# STM32F7.net
KiCad netlist of a schematic drawn in Altium Designer
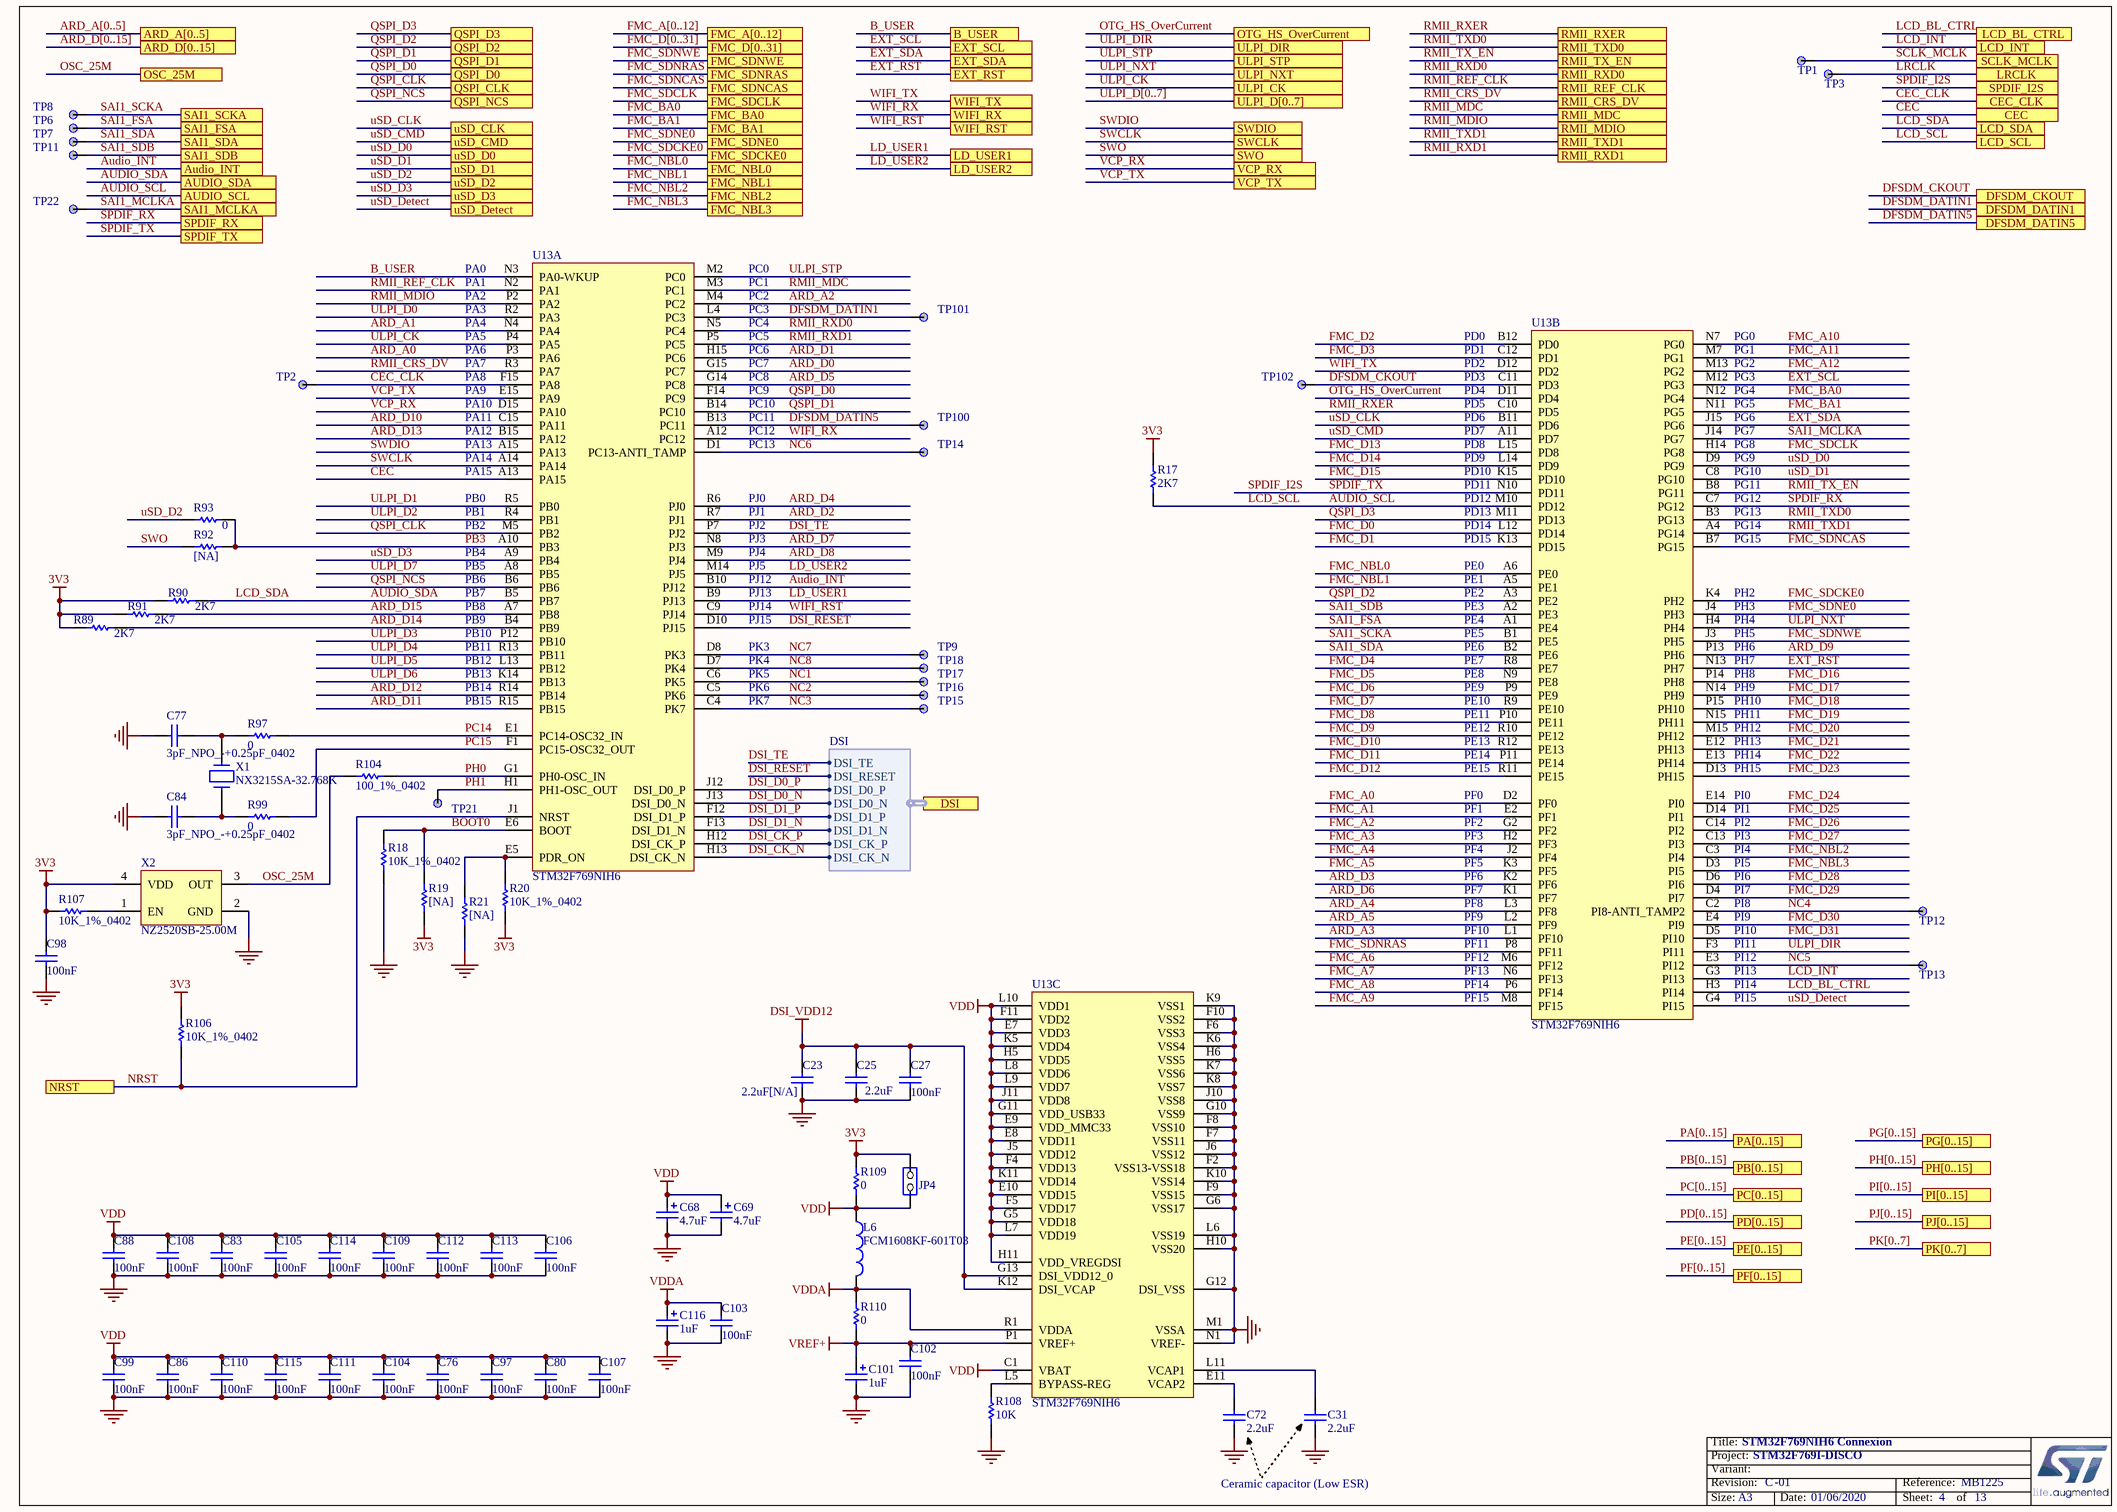
[diagram p0: STM32F7.SchDoc]

(export (version "E")
  (design (tool "Eeschema 10.0.6"))
  (components
    (comp (ref "C23")
      (value "2.2uF[N/A]")
      (footprint "1206C")
      (description "Capacitor,2.2uF,16V, X7R,10%,1206,YAGEO")
      (libsource (lib "MCD_TOOLS_CAPACITOR") (part "Cap_2.2uF_X7R_10%_1206"))
    )
    (comp (ref "C25")
      (value "2.2uF")
      (footprint "0603C")
      (description "Capacitor,2.2uF,10V, X5R,10%,0603,YAGEO")
      (libsource (lib "MCD_TOOLS_CAPACITOR") (part "Cap_2.2uF_X5R_10%_0603"))
    )
    (comp (ref "C27")
      (value "100nF")
      (footprint "0402C")
      (description "Capacitor,100nF,16V,X7R,10%,0402,YAGEO")
      (libsource (lib "MCD_TOOLS_CAPACITOR") (part "Cap_100nF_X7R_10%_0402"))
    )
    (comp (ref "C31")
      (value "2.2uF")
      (footprint "1206C")
      (description "Capacitor,2.2uF,16V, X7R,10%,1206,YAGEO")
      (libsource (lib "MCD_TOOLS") (part "Cap_2.2uF_X7R_10%_1206"))
    )
    (comp (ref "C68")
      (value "4.7uF")
      (footprint "TAN-A")
      (description "Polarized Capacitor,4.7uF,16V,10%,typeA,AVX")
      (libsource (lib "MCD_TOOLS") (part "Cap_4.7uF_POL_10%_TANA"))
    )
    (comp (ref "C69")
      (value "4.7uF")
      (footprint "TAN-A")
      (description "Polarized Capacitor,4.7uF,16V,10%,typeA,AVX")
      (libsource (lib "MCD_TOOLS") (part "Cap_4.7uF_POL_10%_TANA"))
    )
    (comp (ref "C72")
      (value "2.2uF")
      (footprint "1206C")
      (description "Capacitor,2.2uF,16V, X7R,10%,1206,YAGEO")
      (libsource (lib "MCD_TOOLS") (part "Cap_2.2uF_X7R_10%_1206"))
    )
    (comp (ref "C76")
      (value "100nF")
      (footprint "0402C")
      (description "Capacitor,100nF,16V,X7R,10%,0402,YAGEO")
      (libsource (lib "MCD_TOOLS") (part "Cap_100nF_X7R_10%_0402"))
    )
    (comp (ref "C77")
      (value "3pF_NPO_-+0.25pF_0402")
      (footprint "0402C")
      (description "Capacitor, 3pF, 16V, NPO, -+0.25pF, 0402, KEMET")
      (libsource (lib "MCD_TOOLS_CAPACITOR") (part "Cap_4.3pF_NPO_-+0.25pF_0402"))
    )
    (comp (ref "C80")
      (value "100nF")
      (footprint "0402C")
      (description "Capacitor,100nF,16V,X7R,10%,0402,YAGEO")
      (libsource (lib "MCD_TOOLS") (part "Cap_100nF_X7R_10%_0402"))
    )
    (comp (ref "C83")
      (value "100nF")
      (footprint "0402C")
      (description "Capacitor,100nF,16V,X7R,10%,0402,YAGEO")
      (libsource (lib "MCD_TOOLS") (part "Cap_100nF_X7R_10%_0402"))
    )
    (comp (ref "C84")
      (value "3pF_NPO_-+0.25pF_0402")
      (footprint "0402C")
      (description "Capacitor, 3pF, 16V, NPO, -+0.25pF, 0402, KEMET")
      (libsource (lib "MCD_TOOLS_CAPACITOR") (part "Cap_4.3pF_NPO_-+0.25pF_0402"))
    )
    (comp (ref "C86")
      (value "100nF")
      (footprint "0402C")
      (description "Capacitor,100nF,16V,X7R,10%,0402,YAGEO")
      (libsource (lib "MCD_TOOLS") (part "Cap_100nF_X7R_10%_0402"))
    )
    (comp (ref "C88")
      (value "100nF")
      (footprint "0402C")
      (description "Capacitor,100nF,16V,X7R,10%,0402,YAGEO")
      (libsource (lib "MCD_TOOLS") (part "Cap_100nF_X7R_10%_0402"))
    )
    (comp (ref "C97")
      (value "100nF")
      (footprint "0402C")
      (description "Capacitor,100nF,16V,X7R,10%,0402,YAGEO")
      (libsource (lib "MCD_TOOLS") (part "Cap_100nF_X7R_10%_0402"))
    )
    (comp (ref "C98")
      (value "100nF")
      (footprint "0402C")
      (description "Capacitor,100nF,16V,X7R,10%,0402,YAGEO")
      (libsource (lib "MCD_TOOLS") (part "Cap_100nF_X7R_10%_0402"))
    )
    (comp (ref "C99")
      (value "100nF")
      (footprint "0402C")
      (description "Capacitor,100nF,16V,X7R,10%,0402,YAGEO")
      (libsource (lib "MCD_TOOLS") (part "Cap_100nF_X7R_10%_0402"))
    )
    (comp (ref "C101")
      (value "1uF")
      (footprint "TAN-A")
      (description "Polarized Capacitor,1uF,16V,10%,typeA,AVX")
      (libsource (lib "MCD_TOOLS") (part "Cap_1uF_POL_10%_TANA"))
    )
    (comp (ref "C102")
      (value "100nF")
      (footprint "0402C")
      (description "Capacitor,100nF,16V,X7R,10%,0402,YAGEO")
      (libsource (lib "MCD_TOOLS") (part "Cap_100nF_X7R_10%_0402"))
    )
    (comp (ref "C103")
      (value "100nF")
      (footprint "0402C")
      (description "Capacitor,100nF,16V,X7R,10%,0402,YAGEO")
      (libsource (lib "MCD_TOOLS") (part "Cap_100nF_X7R_10%_0402"))
    )
    (comp (ref "C104")
      (value "100nF")
      (footprint "0402C")
      (description "Capacitor,100nF,16V,X7R,10%,0402,YAGEO")
      (libsource (lib "MCD_TOOLS") (part "Cap_100nF_X7R_10%_0402"))
    )
    (comp (ref "C105")
      (value "100nF")
      (footprint "0402C")
      (description "Capacitor,100nF,16V,X7R,10%,0402,YAGEO")
      (libsource (lib "MCD_TOOLS") (part "Cap_100nF_X7R_10%_0402"))
    )
    (comp (ref "C106")
      (value "100nF")
      (footprint "0402C")
      (description "Capacitor,100nF,16V,X7R,10%,0402,YAGEO")
      (libsource (lib "MCD_TOOLS") (part "Cap_100nF_X7R_10%_0402"))
    )
    (comp (ref "C107")
      (value "100nF")
      (footprint "0402C")
      (description "Capacitor,100nF,16V,X7R,10%,0402,YAGEO")
      (libsource (lib "MCD_TOOLS") (part "Cap_100nF_X7R_10%_0402"))
    )
    (comp (ref "C108")
      (value "100nF")
      (footprint "0402C")
      (description "Capacitor,100nF,16V,X7R,10%,0402,YAGEO")
      (libsource (lib "MCD_TOOLS") (part "Cap_100nF_X7R_10%_0402"))
    )
    (comp (ref "C109")
      (value "100nF")
      (footprint "0402C")
      (description "Capacitor,100nF,16V,X7R,10%,0402,YAGEO")
      (libsource (lib "MCD_TOOLS") (part "Cap_100nF_X7R_10%_0402"))
    )
    (comp (ref "C110")
      (value "100nF")
      (footprint "0402C")
      (description "Capacitor,100nF,16V,X7R,10%,0402,YAGEO")
      (libsource (lib "MCD_TOOLS") (part "Cap_100nF_X7R_10%_0402"))
    )
    (comp (ref "C111")
      (value "100nF")
      (footprint "0402C")
      (description "Capacitor,100nF,16V,X7R,10%,0402,YAGEO")
      (libsource (lib "MCD_TOOLS") (part "Cap_100nF_X7R_10%_0402"))
    )
    (comp (ref "C112")
      (value "100nF")
      (footprint "0402C")
      (description "Capacitor,100nF,16V,X7R,10%,0402,YAGEO")
      (libsource (lib "MCD_TOOLS") (part "Cap_100nF_X7R_10%_0402"))
    )
    (comp (ref "C113")
      (value "100nF")
      (footprint "0402C")
      (description "Capacitor,100nF,16V,X7R,10%,0402,YAGEO")
      (libsource (lib "MCD_TOOLS") (part "Cap_100nF_X7R_10%_0402"))
    )
    (comp (ref "C114")
      (value "100nF")
      (footprint "0402C")
      (description "Capacitor,100nF,16V,X7R,10%,0402,YAGEO")
      (libsource (lib "MCD_TOOLS") (part "Cap_100nF_X7R_10%_0402"))
    )
    (comp (ref "C115")
      (value "100nF")
      (footprint "0402C")
      (description "Capacitor,100nF,16V,X7R,10%,0402,YAGEO")
      (libsource (lib "MCD_TOOLS") (part "Cap_100nF_X7R_10%_0402"))
    )
    (comp (ref "C116")
      (value "1uF")
      (footprint "TAN-A")
      (description "Polarized Capacitor,1uF,16V,10%,typeA,AVX")
      (libsource (lib "MCD_TOOLS") (part "Cap_1uF_POL_10%_TANA"))
    )
    (comp (ref "JP4") (value "JP2") (footprint "SIP2") (libsource (lib "MCD_TOOLS_CONNECTOR") (part "JP2")))
    (comp (ref "L6")
      (value "FCM1608KF-601T03")
      (footprint "0603L")
      (description "Bead,600R,350mA,0603,FCM1608KF-601T03,Tai-tech")
      (libsource (lib "MCD_TOOLS") (part "BEAD_600R_350MA_0603"))
    )
    (comp (ref "R17")
      (value "2K7")
      (footprint "0402R")
      (description "Resistor,2K7,0402,1%,YAGEO")
      (libsource (lib "MCD_TOOLS") (part "Res_2K7_1%_0402"))
    )
    (comp (ref "R18")
      (value "10K_1%_0402")
      (footprint "0402R")
      (description "Resistor,10K,0402,1%,YAGEO")
      (libsource (lib "MCD_TOOLS") (part "Res_10K_1%_0402"))
    )
    (comp (ref "R19")
      (value "[NA]")
      (footprint "0402R")
      (description "Resistor,[NA],0402")
      (libsource (lib "MCD_TOOLS") (part "Res_NA_0402"))
    )
    (comp (ref "R20")
      (value "10K_1%_0402")
      (footprint "0402R")
      (description "Resistor,10K,0402,1%,YAGEO")
      (libsource (lib "MCD_TOOLS") (part "Res_10K_1%_0402"))
    )
    (comp (ref "R21")
      (value "[NA]")
      (footprint "0402R")
      (description "Resistor,[NA],0402")
      (libsource (lib "MCD_TOOLS") (part "Res_NA_0402"))
    )
    (comp (ref "R89")
      (value "2K7")
      (footprint "0402R")
      (description "Resistor,2K7,0402,1%,YAGEO")
      (libsource (lib "MCD_TOOLS") (part "Res_2K7_1%_0402"))
    )
    (comp (ref "R90")
      (value "2K7")
      (footprint "0402R")
      (description "Resistor,2K7,0402,1%,YAGEO")
      (libsource (lib "MCD_TOOLS") (part "Res_2K7_1%_0402"))
    )
    (comp (ref "R91")
      (value "2K7")
      (footprint "0402R")
      (description "Resistor,2K7,0402,1%,YAGEO")
      (libsource (lib "MCD_TOOLS") (part "Res_2K7_1%_0402"))
    )
    (comp (ref "R92")
      (value "[NA]")
      (footprint "0402R")
      (description "Resistor,[NA],0402")
      (libsource (lib "MCD_TOOLS_RESISTOR") (part "Res_NA_0402"))
    )
    (comp (ref "R93")
      (value "0")
      (footprint "0402R")
      (description "Resistor,0,0402,5%,YAGEO")
      (libsource (lib "MCD_TOOLS_RESISTOR") (part "Res_0_5%_0402"))
    )
    (comp (ref "R97")
      (value "0")
      (footprint "0402R")
      (description "Resistor,0,0402,5%,YAGEO")
      (libsource (lib "MCD_TOOLS") (part "Res_0_5%_0402"))
    )
    (comp (ref "R99")
      (value "0")
      (footprint "0402R")
      (description "Resistor,0,0402,5%,YAGEO")
      (libsource (lib "MCD_TOOLS") (part "Res_0_5%_0402"))
    )
    (comp (ref "R104")
      (value "100_1%_0402")
      (footprint "0402R")
      (description "Resistor,100,0402,1%,YAGEO")
      (libsource (lib "MCD_TOOLS") (part "Res_100_1%_0402"))
    )
    (comp (ref "R106")
      (value "10K_1%_0402")
      (footprint "0402R")
      (description "Resistor,10K,0402,1%,YAGEO")
      (libsource (lib "MCD_TOOLS") (part "Res_10K_1%_0402"))
    )
    (comp (ref "R107")
      (value "10K_1%_0402")
      (footprint "0402R")
      (description "Resistor,10K,0402,1%,YAGEO")
      (libsource (lib "MCD_TOOLS") (part "Res_10K_1%_0402"))
    )
    (comp (ref "R108")
      (value "10K")
      (footprint "0402R")
      (description "Resistor,10K,0402,1%,YAGEO")
      (libsource (lib "MCD_TOOLS") (part "Res_10K_1%_0402"))
    )
    (comp (ref "R109")
      (value "0")
      (footprint "0603R-GS")
      (description "Resistor,0,0603,5%,YAGEO")
      (libsource (lib "MCD_TOOLS") (part "Res_0_5%_0603"))
    )
    (comp (ref "R110")
      (value "0")
      (footprint "0603R-GS")
      (description "Resistor,0,0603,5%,YAGEO")
      (libsource (lib "MCD_TOOLS") (part "Res_0_5%_0603"))
    )
    (comp (ref "TP1")
      (value "TP")
      (footprint "TP_C40")
      (description "Test Point")
      (libsource (lib "MCD_TOOLS_CONNECTOR") (part "TP"))
    )
    (comp (ref "TP2")
      (value "TP")
      (footprint "TP_C40")
      (description "Test Point")
      (libsource (lib "MCD_TOOLS_CONNECTOR") (part "TP"))
    )
    (comp (ref "TP3")
      (value "TP")
      (footprint "TP_C40")
      (description "Test Point")
      (libsource (lib "MCD_TOOLS_CONNECTOR") (part "TP"))
    )
    (comp (ref "TP6")
      (value "TP")
      (footprint "TP_C40")
      (description "Test Point")
      (libsource (lib "MCD_TOOLS_CONNECTOR") (part "TP"))
    )
    (comp (ref "TP7")
      (value "TP")
      (footprint "TP_C40")
      (description "Test Point")
      (libsource (lib "MCD_TOOLS_CONNECTOR") (part "TP"))
    )
    (comp (ref "TP8")
      (value "TP")
      (footprint "TP_C40")
      (description "Test Point")
      (libsource (lib "MCD_TOOLS_CONNECTOR") (part "TP"))
    )
    (comp (ref "TP9")
      (value "TP")
      (footprint "TP_C40")
      (description "Test Point")
      (libsource (lib "MCD_TOOLS_CONNECTOR") (part "TP"))
    )
    (comp (ref "TP11")
      (value "TP")
      (footprint "TP_C40")
      (description "Test Point")
      (libsource (lib "MCD_TOOLS_CONNECTOR") (part "TP"))
    )
    (comp (ref "TP12")
      (value "TP")
      (footprint "TP_C40")
      (description "Test Point")
      (libsource (lib "MCD_TOOLS_CONNECTOR") (part "TP"))
    )
    (comp (ref "TP13")
      (value "TP")
      (footprint "TP_C40")
      (description "Test Point")
      (libsource (lib "MCD_TOOLS_CONNECTOR") (part "TP"))
    )
    (comp (ref "TP14")
      (value "TP")
      (footprint "TP_C40")
      (description "Test Point")
      (libsource (lib "MCD_TOOLS_CONNECTOR") (part "TP"))
    )
    (comp (ref "TP15")
      (value "TP")
      (footprint "TP_C40")
      (description "Test Point")
      (libsource (lib "MCD_TOOLS_CONNECTOR") (part "TP"))
    )
    (comp (ref "TP16")
      (value "TP")
      (footprint "TP_C40")
      (description "Test Point")
      (libsource (lib "MCD_TOOLS_CONNECTOR") (part "TP"))
    )
    (comp (ref "TP17")
      (value "TP")
      (footprint "TP_C40")
      (description "Test Point")
      (libsource (lib "MCD_TOOLS_CONNECTOR") (part "TP"))
    )
    (comp (ref "TP18")
      (value "TP")
      (footprint "TP_C40")
      (description "Test Point")
      (libsource (lib "MCD_TOOLS_CONNECTOR") (part "TP"))
    )
    (comp (ref "TP21")
      (value "TP")
      (footprint "TP_C40")
      (description "Test Point")
      (libsource (lib "MCD_TOOLS_CONNECTOR") (part "TP"))
    )
    (comp (ref "TP22")
      (value "TP")
      (footprint "TP_C40")
      (description "Test Point")
      (libsource (lib "MCD_TOOLS_CONNECTOR") (part "TP"))
    )
    (comp (ref "TP100")
      (value "TP")
      (footprint "TP_C40")
      (description "Test Point")
      (libsource (lib "MCD_TOOLS_CONNECTOR") (part "TP"))
    )
    (comp (ref "TP101")
      (value "TP")
      (footprint "TP_C40")
      (description "Test Point")
      (libsource (lib "MCD_TOOLS_CONNECTOR") (part "TP"))
    )
    (comp (ref "TP102")
      (value "TP")
      (footprint "TP_C40")
      (description "Test Point")
      (libsource (lib "MCD_TOOLS_CONNECTOR") (part "TP"))
    )
    (comp (ref "U13")
      (value "STM32F769NIH6")
      (footprint "BGA216_0R8_13X13")
      (description "STM32F769NIH6 (STM32F7 Big Birdie) TBGA216")
      (libsource (lib "MCD_TOOLS_MCU") (part "STM32F769NIH6U"))
    )
    (comp (ref "X1")
      (value "NX3215SA-32.768K")
      (footprint "XTAL_2SM_3R2X1R5")
      (description "Crystal 32.768kHz, 6pF, -+20PPM, R=50K, SMD")
      (libsource (lib "MCD_TOOLS") (part "XTAL_32K_NX3215SA"))
    )
    (comp (ref "X2")
      (value "NZ2520SB-25.00M")
      (footprint "OSC_4SM_2R5X2")
      (description "Oscillator 25.00Mhz, -+50PPM, 3.3V, Temp -55 to +125°C")
      (libsource (lib "MCD_TOOLS_MISCELLANEOUS") (part "OSC_25M_NZ2520SB"))
    )
  )
  (nets
    (net (code "165") (name "/ARD_A0") (class "Default")
      (node (ref "U13") (pin "P3") (pinfunction "PA6_P3") (pintype "passive"))
    )
    (net (code "166") (name "/ARD_A1") (class "Default")
      (node (ref "U13") (pin "N4") (pinfunction "PA4_N4") (pintype "passive"))
    )
    (net (code "167") (name "/ARD_A2") (class "Default")
      (node (ref "U13") (pin "M4") (pinfunction "PC2_M4") (pintype "passive"))
    )
    (net (code "168") (name "/ARD_A3") (class "Default")
      (node (ref "U13") (pin "L1") (pinfunction "PF10_L1") (pintype "passive"))
    )
    (net (code "169") (name "/ARD_A4") (class "Default")
      (node (ref "U13") (pin "L3") (pinfunction "PF8_L3") (pintype "passive"))
    )
    (net (code "170") (name "/ARD_A5") (class "Default")
      (node (ref "U13") (pin "L2") (pinfunction "PF9_L2") (pintype "passive"))
    )
    (net (code "172") (name "/ARD_D0") (class "Default")
      (node (ref "U13") (pin "G15") (pinfunction "PC7_G15") (pintype "passive"))
    )
    (net (code "173") (name "/ARD_D1") (class "Default")
      (node (ref "U13") (pin "H15") (pinfunction "PC6_H15") (pintype "passive"))
    )
    (net (code "174") (name "/ARD_D2") (class "Default")
      (node (ref "U13") (pin "R7") (pinfunction "PJ1_R7") (pintype "passive"))
    )
    (net (code "175") (name "/ARD_D3") (class "Default")
      (node (ref "U13") (pin "K2") (pinfunction "PF6_K2") (pintype "passive"))
    )
    (net (code "176") (name "/ARD_D4") (class "Default")
      (node (ref "U13") (pin "R6") (pinfunction "PJ0_R6") (pintype "passive"))
    )
    (net (code "177") (name "/ARD_D5") (class "Default")
      (node (ref "U13") (pin "G14") (pinfunction "PC8_G14") (pintype "passive"))
    )
    (net (code "178") (name "/ARD_D6") (class "Default")
      (node (ref "U13") (pin "K1") (pinfunction "PF7_K1") (pintype "passive"))
    )
    (net (code "179") (name "/ARD_D7") (class "Default")
      (node (ref "U13") (pin "N8") (pinfunction "PJ3_N8") (pintype "passive"))
    )
    (net (code "180") (name "/ARD_D8") (class "Default")
      (node (ref "U13") (pin "M9") (pinfunction "PJ4_M9") (pintype "passive"))
    )
    (net (code "181") (name "/ARD_D9") (class "Default")
      (node (ref "U13") (pin "P13") (pinfunction "PH6_P13") (pintype "passive"))
    )
    (net (code "182") (name "/ARD_D10") (class "Default")
      (node (ref "U13") (pin "C15") (pinfunction "PA11_C15") (pintype "passive"))
    )
    (net (code "183") (name "/ARD_D11") (class "Default")
      (node (ref "U13") (pin "R15") (pinfunction "PB15_R15") (pintype "passive"))
    )
    (net (code "184") (name "/ARD_D12") (class "Default")
      (node (ref "U13") (pin "R14") (pinfunction "PB14_R14") (pintype "passive"))
    )
    (net (code "185") (name "/ARD_D13") (class "Default")
      (node (ref "U13") (pin "B15") (pinfunction "PA12_B15") (pintype "passive"))
    )
    (net (code "186") (name "/ARD_D14") (class "Default")
      (node (ref "R89") (pin "2") (pinfunction "2_2") (pintype "passive"))
      (node (ref "U13") (pin "B4") (pinfunction "PB9_B4") (pintype "passive"))
    )
    (net (code "187") (name "/ARD_D15") (class "Default")
      (node (ref "R91") (pin "2") (pinfunction "2_2") (pintype "passive"))
      (node (ref "U13") (pin "A7") (pinfunction "PB8_A7") (pintype "passive"))
    )
    (net (code "189") (name "/AUDIO_SCL") (class "Default")
      (node (ref "R17") (pin "1") (pinfunction "1_1") (pintype "passive"))
      (node (ref "U13") (pin "M10") (pinfunction "PD12_M10") (pintype "passive"))
    )
    (net (code "190") (name "/AUDIO_SDA") (class "Default")
      (node (ref "R90") (pin "2") (pinfunction "2_2") (pintype "passive"))
      (node (ref "U13") (pin "B5") (pinfunction "PB7_B5") (pintype "passive"))
    )
    (net (code "191") (name "/Audio_INT") (class "Default")
      (node (ref "U13") (pin "B10") (pinfunction "PJ12_B10") (pintype "passive"))
    )
    (net (code "192") (name "/BOOT0") (class "Default")
      (node (ref "R18") (pin "2") (pinfunction "2_2") (pintype "passive"))
      (node (ref "R19") (pin "2") (pinfunction "2_2") (pintype "passive"))
      (node (ref "U13") (pin "E6") (pinfunction "BOOT_E6") (pintype "passive"))
    )
    (net (code "193") (name "/B_USER") (class "Default")
      (node (ref "U13") (pin "N3") (pinfunction "PA0-WKUP_N3") (pintype "passive"))
    )
    (net (code "194") (name "/CEC") (class "Default")
      (node (ref "U13") (pin "A13") (pinfunction "PA15_A13") (pintype "passive"))
    )
    (net (code "195") (name "/CEC_CLK") (class "Default")
      (node (ref "TP2") (pin "1") (pinfunction "1_1") (pintype "passive"))
      (node (ref "U13") (pin "F15") (pinfunction "PA8_F15") (pintype "passive"))
    )
    (net (code "196") (name "/DFSDM_CKOUT") (class "Default")
      (node (ref "TP102") (pin "1") (pinfunction "1_1") (pintype "passive"))
      (node (ref "U13") (pin "C11") (pinfunction "PD3_C11") (pintype "passive"))
    )
    (net (code "197") (name "/DFSDM_DATIN1") (class "Default")
      (node (ref "TP101") (pin "1") (pinfunction "1_1") (pintype "passive"))
      (node (ref "U13") (pin "L4") (pinfunction "PC3_L4") (pintype "passive"))
    )
    (net (code "198") (name "/DFSDM_DATIN5") (class "Default")
      (node (ref "TP100") (pin "1") (pinfunction "1_1") (pintype "passive"))
      (node (ref "U13") (pin "B13") (pinfunction "PC11_B13") (pintype "passive"))
    )
    (net (code "199") (name "/DSI_CK_N") (class "Default")
      (node (ref "U13") (pin "H13") (pinfunction "DSI_CK_N_H13") (pintype "passive"))
    )
    (net (code "200") (name "/DSI_CK_P") (class "Default")
      (node (ref "U13") (pin "H12") (pinfunction "DSI_CK_P_H12") (pintype "passive"))
    )
    (net (code "201") (name "/DSI_D0_N") (class "Default")
      (node (ref "U13") (pin "J13") (pinfunction "DSI_D0_N_J13") (pintype "passive"))
    )
    (net (code "202") (name "/DSI_D0_P") (class "Default")
      (node (ref "U13") (pin "J12") (pinfunction "DSI_D0_P_J12") (pintype "passive"))
    )
    (net (code "203") (name "/DSI_D1_N") (class "Default")
      (node (ref "U13") (pin "F13") (pinfunction "DSI_D1_N_F13") (pintype "passive"))
    )
    (net (code "204") (name "/DSI_D1_P") (class "Default")
      (node (ref "U13") (pin "F12") (pinfunction "DSI_D1_P_F12") (pintype "passive"))
    )
    (net (code "205") (name "/DSI_RESET") (class "Default")
      (node (ref "U13") (pin "D10") (pinfunction "PJ15_D10") (pintype "passive"))
    )
    (net (code "206") (name "/DSI_TE") (class "Default")
      (node (ref "U13") (pin "P7") (pinfunction "PJ2_P7") (pintype "passive"))
    )
    (net (code "207") (name "/EXT_RST") (class "Default")
      (node (ref "U13") (pin "N13") (pinfunction "PH7_N13") (pintype "passive"))
    )
    (net (code "208") (name "/EXT_SCL") (class "Default")
      (node (ref "U13") (pin "M12") (pinfunction "PG3_M12") (pintype "passive"))
    )
    (net (code "209") (name "/EXT_SDA") (class "Default")
      (node (ref "U13") (pin "J15") (pinfunction "PG6_J15") (pintype "passive"))
    )
    (net (code "210") (name "/FMC_A0") (class "Default")
      (node (ref "U13") (pin "D2") (pinfunction "PF0_D2") (pintype "passive"))
    )
    (net (code "211") (name "/FMC_A1") (class "Default")
      (node (ref "U13") (pin "E2") (pinfunction "PF1_E2") (pintype "passive"))
    )
    (net (code "212") (name "/FMC_A2") (class "Default")
      (node (ref "U13") (pin "G2") (pinfunction "PF2_G2") (pintype "passive"))
    )
    (net (code "213") (name "/FMC_A3") (class "Default")
      (node (ref "U13") (pin "H2") (pinfunction "PF3_H2") (pintype "passive"))
    )
    (net (code "214") (name "/FMC_A4") (class "Default")
      (node (ref "U13") (pin "J2") (pinfunction "PF4_J2") (pintype "passive"))
    )
    (net (code "215") (name "/FMC_A5") (class "Default")
      (node (ref "U13") (pin "K3") (pinfunction "PF5_K3") (pintype "passive"))
    )
    (net (code "216") (name "/FMC_A6") (class "Default")
      (node (ref "U13") (pin "M6") (pinfunction "PF12_M6") (pintype "passive"))
    )
    (net (code "217") (name "/FMC_A7") (class "Default")
      (node (ref "U13") (pin "N6") (pinfunction "PF13_N6") (pintype "passive"))
    )
    (net (code "218") (name "/FMC_A8") (class "Default")
      (node (ref "U13") (pin "P6") (pinfunction "PF14_P6") (pintype "passive"))
    )
    (net (code "219") (name "/FMC_A9") (class "Default")
      (node (ref "U13") (pin "M8") (pinfunction "PF15_M8") (pintype "passive"))
    )
    (net (code "220") (name "/FMC_A10") (class "Default")
      (node (ref "U13") (pin "N7") (pinfunction "PG0_N7") (pintype "passive"))
    )
    (net (code "221") (name "/FMC_A11") (class "Default")
      (node (ref "U13") (pin "M7") (pinfunction "PG1_M7") (pintype "passive"))
    )
    (net (code "222") (name "/FMC_A12") (class "Default")
      (node (ref "U13") (pin "M13") (pinfunction "PG2_M13") (pintype "passive"))
    )
    (net (code "224") (name "/FMC_BA0") (class "Default")
      (node (ref "U13") (pin "N12") (pinfunction "PG4_N12") (pintype "passive"))
    )
    (net (code "225") (name "/FMC_BA1") (class "Default")
      (node (ref "U13") (pin "N11") (pinfunction "PG5_N11") (pintype "passive"))
    )
    (net (code "226") (name "/FMC_D0") (class "Default")
      (node (ref "U13") (pin "L12") (pinfunction "PD14_L12") (pintype "passive"))
    )
    (net (code "227") (name "/FMC_D1") (class "Default")
      (node (ref "U13") (pin "K13") (pinfunction "PD15_K13") (pintype "passive"))
    )
    (net (code "228") (name "/FMC_D2") (class "Default")
      (node (ref "U13") (pin "B12") (pinfunction "PD0_B12") (pintype "passive"))
    )
    (net (code "229") (name "/FMC_D3") (class "Default")
      (node (ref "U13") (pin "C12") (pinfunction "PD1_C12") (pintype "passive"))
    )
    (net (code "230") (name "/FMC_D4") (class "Default")
      (node (ref "U13") (pin "R8") (pinfunction "PE7_R8") (pintype "passive"))
    )
    (net (code "231") (name "/FMC_D5") (class "Default")
      (node (ref "U13") (pin "N9") (pinfunction "PE8_N9") (pintype "passive"))
    )
    (net (code "232") (name "/FMC_D6") (class "Default")
      (node (ref "U13") (pin "P9") (pinfunction "PE9_P9") (pintype "passive"))
    )
    (net (code "233") (name "/FMC_D7") (class "Default")
      (node (ref "U13") (pin "R9") (pinfunction "PE10_R9") (pintype "passive"))
    )
    (net (code "234") (name "/FMC_D8") (class "Default")
      (node (ref "U13") (pin "P10") (pinfunction "PE11_P10") (pintype "passive"))
    )
    (net (code "235") (name "/FMC_D9") (class "Default")
      (node (ref "U13") (pin "R10") (pinfunction "PE12_R10") (pintype "passive"))
    )
    (net (code "236") (name "/FMC_D10") (class "Default")
      (node (ref "U13") (pin "R12") (pinfunction "PE13_R12") (pintype "passive"))
    )
    (net (code "237") (name "/FMC_D11") (class "Default")
      (node (ref "U13") (pin "P11") (pinfunction "PE14_P11") (pintype "passive"))
    )
    (net (code "238") (name "/FMC_D12") (class "Default")
      (node (ref "U13") (pin "R11") (pinfunction "PE15_R11") (pintype "passive"))
    )
    (net (code "239") (name "/FMC_D13") (class "Default")
      (node (ref "U13") (pin "L15") (pinfunction "PD8_L15") (pintype "passive"))
    )
    (net (code "240") (name "/FMC_D14") (class "Default")
      (node (ref "U13") (pin "L14") (pinfunction "PD9_L14") (pintype "passive"))
    )
    (net (code "241") (name "/FMC_D15") (class "Default")
      (node (ref "U13") (pin "K15") (pinfunction "PD10_K15") (pintype "passive"))
    )
    (net (code "242") (name "/FMC_D16") (class "Default")
      (node (ref "U13") (pin "P14") (pinfunction "PH8_P14") (pintype "passive"))
    )
    (net (code "243") (name "/FMC_D17") (class "Default")
      (node (ref "U13") (pin "N14") (pinfunction "PH9_N14") (pintype "passive"))
    )
    (net (code "244") (name "/FMC_D18") (class "Default")
      (node (ref "U13") (pin "P15") (pinfunction "PH10_P15") (pintype "passive"))
    )
    (net (code "245") (name "/FMC_D19") (class "Default")
      (node (ref "U13") (pin "N15") (pinfunction "PH11_N15") (pintype "passive"))
    )
    (net (code "246") (name "/FMC_D20") (class "Default")
      (node (ref "U13") (pin "M15") (pinfunction "PH12_M15") (pintype "passive"))
    )
    (net (code "247") (name "/FMC_D21") (class "Default")
      (node (ref "U13") (pin "E12") (pinfunction "PH13_E12") (pintype "passive"))
    )
    (net (code "248") (name "/FMC_D22") (class "Default")
      (node (ref "U13") (pin "E13") (pinfunction "PH14_E13") (pintype "passive"))
    )
    (net (code "249") (name "/FMC_D23") (class "Default")
      (node (ref "U13") (pin "D13") (pinfunction "PH15_D13") (pintype "passive"))
    )
    (net (code "250") (name "/FMC_D24") (class "Default")
      (node (ref "U13") (pin "E14") (pinfunction "PI0_E14") (pintype "passive"))
    )
    (net (code "251") (name "/FMC_D25") (class "Default")
      (node (ref "U13") (pin "D14") (pinfunction "PI1_D14") (pintype "passive"))
    )
    (net (code "252") (name "/FMC_D26") (class "Default")
      (node (ref "U13") (pin "C14") (pinfunction "PI2_C14") (pintype "passive"))
    )
    (net (code "253") (name "/FMC_D27") (class "Default")
      (node (ref "U13") (pin "C13") (pinfunction "PI3_C13") (pintype "passive"))
    )
    (net (code "254") (name "/FMC_D28") (class "Default")
      (node (ref "U13") (pin "D6") (pinfunction "PI6_D6") (pintype "passive"))
    )
    (net (code "255") (name "/FMC_D29") (class "Default")
      (node (ref "U13") (pin "D4") (pinfunction "PI7_D4") (pintype "passive"))
    )
    (net (code "256") (name "/FMC_D30") (class "Default")
      (node (ref "U13") (pin "E4") (pinfunction "PI9_E4") (pintype "passive"))
    )
    (net (code "257") (name "/FMC_D31") (class "Default")
      (node (ref "U13") (pin "D5") (pinfunction "PI10_D5") (pintype "passive"))
    )
    (net (code "259") (name "/FMC_NBL0") (class "Default")
      (node (ref "U13") (pin "A6") (pinfunction "PE0_A6") (pintype "passive"))
    )
    (net (code "260") (name "/FMC_NBL1") (class "Default")
      (node (ref "U13") (pin "A5") (pinfunction "PE1_A5") (pintype "passive"))
    )
    (net (code "261") (name "/FMC_NBL2") (class "Default")
      (node (ref "U13") (pin "C3") (pinfunction "PI4_C3") (pintype "passive"))
    )
    (net (code "262") (name "/FMC_NBL3") (class "Default")
      (node (ref "U13") (pin "D3") (pinfunction "PI5_D3") (pintype "passive"))
    )
    (net (code "263") (name "/FMC_SDCKE0") (class "Default")
      (node (ref "U13") (pin "K4") (pinfunction "PH2_K4") (pintype "passive"))
    )
    (net (code "264") (name "/FMC_SDCLK") (class "Default")
      (node (ref "U13") (pin "H14") (pinfunction "PG8_H14") (pintype "passive"))
    )
    (net (code "265") (name "/FMC_SDNCAS") (class "Default")
      (node (ref "U13") (pin "B7") (pinfunction "PG15_B7") (pintype "passive"))
    )
    (net (code "266") (name "/FMC_SDNE0") (class "Default")
      (node (ref "U13") (pin "J4") (pinfunction "PH3_J4") (pintype "passive"))
    )
    (net (code "267") (name "/FMC_SDNRAS") (class "Default")
      (node (ref "U13") (pin "P8") (pinfunction "PF11_P8") (pintype "passive"))
    )
    (net (code "268") (name "/FMC_SDNWE") (class "Default")
      (node (ref "U13") (pin "J3") (pinfunction "PH5_J3") (pintype "passive"))
    )
    (net (code "269") (name "/LCD_BL_CTRL") (class "Default")
      (node (ref "U13") (pin "H3") (pinfunction "PI14_H3") (pintype "passive"))
    )
    (net (code "270") (name "/LCD_INT") (class "Default")
      (node (ref "U13") (pin "G3") (pinfunction "PI13_G3") (pintype "passive"))
    )
    (net (code "271") (name "/LD_USER1") (class "Default")
      (node (ref "U13") (pin "B9") (pinfunction "PJ13_B9") (pintype "passive"))
    )
    (net (code "272") (name "/LD_USER2") (class "Default")
      (node (ref "U13") (pin "M14") (pinfunction "PJ5_M14") (pintype "passive"))
    )
    (net (code "273") (name "/LRCLK") (class "Default")
      (node (ref "TP3") (pin "1") (pinfunction "1_1") (pintype "passive"))
    )
    (net (code "274") (name "/NC1") (class "Default")
      (node (ref "TP17") (pin "1") (pinfunction "1_1") (pintype "passive"))
      (node (ref "U13") (pin "C6") (pinfunction "PK5_C6") (pintype "passive"))
    )
    (net (code "275") (name "/NC2") (class "Default")
      (node (ref "TP16") (pin "1") (pinfunction "1_1") (pintype "passive"))
      (node (ref "U13") (pin "C5") (pinfunction "PK6_C5") (pintype "passive"))
    )
    (net (code "276") (name "/NC3") (class "Default")
      (node (ref "TP15") (pin "1") (pinfunction "1_1") (pintype "passive"))
      (node (ref "U13") (pin "C4") (pinfunction "PK7_C4") (pintype "passive"))
    )
    (net (code "277") (name "/NC4") (class "Default")
      (node (ref "TP12") (pin "1") (pinfunction "1_1") (pintype "passive"))
      (node (ref "U13") (pin "C2") (pinfunction "PI8-ANTI_TAMP2_C2") (pintype "passive"))
    )
    (net (code "278") (name "/NC5") (class "Default")
      (node (ref "TP13") (pin "1") (pinfunction "1_1") (pintype "passive"))
      (node (ref "U13") (pin "E3") (pinfunction "PI12_E3") (pintype "passive"))
    )
    (net (code "279") (name "/NC6") (class "Default")
      (node (ref "TP14") (pin "1") (pinfunction "1_1") (pintype "passive"))
      (node (ref "U13") (pin "D1") (pinfunction "PC13-ANTI_TAMP_D1") (pintype "passive"))
    )
    (net (code "280") (name "/NC7") (class "Default")
      (node (ref "TP9") (pin "1") (pinfunction "1_1") (pintype "passive"))
      (node (ref "U13") (pin "D8") (pinfunction "PK3_D8") (pintype "passive"))
    )
    (net (code "281") (name "/NC8") (class "Default")
      (node (ref "TP18") (pin "1") (pinfunction "1_1") (pintype "passive"))
      (node (ref "U13") (pin "D7") (pinfunction "PK4_D7") (pintype "passive"))
    )
    (net (code "282") (name "/NRST") (class "Default")
      (node (ref "R106") (pin "1") (pinfunction "1_1") (pintype "passive"))
      (node (ref "U13") (pin "J1") (pinfunction "NRST_J1") (pintype "passive"))
    )
    (net (code "283") (name "/OSC_25M") (class "Default")
      (node (ref "R104") (pin "1") (pinfunction "1_1") (pintype "passive"))
      (node (ref "X2") (pin "3") (pinfunction "OUT_3") (pintype "passive"))
    )
    (net (code "284") (name "/OTG_HS_OverCurrent") (class "Default")
      (node (ref "U13") (pin "D11") (pinfunction "PD4_D11") (pintype "passive"))
    )
    (net (code "286") (name "/PB3") (class "Default")
      (node (ref "R92") (pin "2") (pinfunction "2_2") (pintype "passive"))
      (node (ref "R93") (pin "2") (pinfunction "2_2") (pintype "passive"))
      (node (ref "U13") (pin "A10") (pinfunction "PB3_A10") (pintype "passive"))
    )
    (net (code "288") (name "/PC14") (class "Default")
      (node (ref "R97") (pin "2") (pinfunction "2_2") (pintype "passive"))
      (node (ref "U13") (pin "E1") (pinfunction "PC14-OSC32_IN_E1") (pintype "passive"))
    )
    (net (code "289") (name "/PC15") (class "Default")
      (node (ref "R99") (pin "2") (pinfunction "2_2") (pintype "passive"))
      (node (ref "U13") (pin "F1") (pinfunction "PC15-OSC32_OUT_F1") (pintype "passive"))
    )
    (net (code "295") (name "/PH0") (class "Default")
      (node (ref "R104") (pin "2") (pinfunction "2_2") (pintype "passive"))
      (node (ref "U13") (pin "G1") (pinfunction "PH0-OSC_IN_G1") (pintype "passive"))
    )
    (net (code "296") (name "/PH1") (class "Default")
      (node (ref "TP21") (pin "1") (pinfunction "1_1") (pintype "passive"))
      (node (ref "U13") (pin "H1") (pinfunction "PH1-OSC_OUT_H1") (pintype "passive"))
    )
    (net (code "301") (name "/QSPI_CLK") (class "Default")
      (node (ref "U13") (pin "M5") (pinfunction "PB2_M5") (pintype "passive"))
    )
    (net (code "302") (name "/QSPI_D0") (class "Default")
      (node (ref "U13") (pin "F14") (pinfunction "PC9_F14") (pintype "passive"))
    )
    (net (code "303") (name "/QSPI_D1") (class "Default")
      (node (ref "U13") (pin "B14") (pinfunction "PC10_B14") (pintype "passive"))
    )
    (net (code "304") (name "/QSPI_D2") (class "Default")
      (node (ref "U13") (pin "A3") (pinfunction "PE2_A3") (pintype "passive"))
    )
    (net (code "305") (name "/QSPI_D3") (class "Default")
      (node (ref "U13") (pin "M11") (pinfunction "PD13_M11") (pintype "passive"))
    )
    (net (code "306") (name "/QSPI_NCS") (class "Default")
      (node (ref "U13") (pin "B6") (pinfunction "PB6_B6") (pintype "passive"))
    )
    (net (code "307") (name "/RMII_CRS_DV") (class "Default")
      (node (ref "U13") (pin "R3") (pinfunction "PA7_R3") (pintype "passive"))
    )
    (net (code "308") (name "/RMII_MDC") (class "Default")
      (node (ref "U13") (pin "M3") (pinfunction "PC1_M3") (pintype "passive"))
    )
    (net (code "309") (name "/RMII_MDIO") (class "Default")
      (node (ref "U13") (pin "P2") (pinfunction "PA2_P2") (pintype "passive"))
    )
    (net (code "310") (name "/RMII_REF_CLK") (class "Default")
      (node (ref "U13") (pin "N2") (pinfunction "PA1_N2") (pintype "passive"))
    )
    (net (code "311") (name "/RMII_RXD0") (class "Default")
      (node (ref "U13") (pin "N5") (pinfunction "PC4_N5") (pintype "passive"))
    )
    (net (code "312") (name "/RMII_RXD1") (class "Default")
      (node (ref "U13") (pin "P5") (pinfunction "PC5_P5") (pintype "passive"))
    )
    (net (code "313") (name "/RMII_RXER") (class "Default")
      (node (ref "U13") (pin "C10") (pinfunction "PD5_C10") (pintype "passive"))
    )
    (net (code "314") (name "/RMII_TXD0") (class "Default")
      (node (ref "U13") (pin "B3") (pinfunction "PG13_B3") (pintype "passive"))
    )
    (net (code "315") (name "/RMII_TXD1") (class "Default")
      (node (ref "U13") (pin "A4") (pinfunction "PG14_A4") (pintype "passive"))
    )
    (net (code "316") (name "/RMII_TX_EN") (class "Default")
      (node (ref "U13") (pin "B8") (pinfunction "PG11_B8") (pintype "passive"))
    )
    (net (code "317") (name "/SAI1_FSA") (class "Default")
      (node (ref "TP6") (pin "1") (pinfunction "1_1") (pintype "passive"))
      (node (ref "U13") (pin "A1") (pinfunction "PE4_A1") (pintype "passive"))
    )
    (net (code "318") (name "/SAI1_MCLKA") (class "Default")
      (node (ref "TP22") (pin "1") (pinfunction "1_1") (pintype "passive"))
      (node (ref "U13") (pin "J14") (pinfunction "PG7_J14") (pintype "passive"))
    )
    (net (code "319") (name "/SAI1_SCKA") (class "Default")
      (node (ref "TP8") (pin "1") (pinfunction "1_1") (pintype "passive"))
      (node (ref "U13") (pin "B1") (pinfunction "PE5_B1") (pintype "passive"))
    )
    (net (code "320") (name "/SAI1_SDA") (class "Default")
      (node (ref "TP7") (pin "1") (pinfunction "1_1") (pintype "passive"))
      (node (ref "U13") (pin "B2") (pinfunction "PE6_B2") (pintype "passive"))
    )
    (net (code "321") (name "/SAI1_SDB") (class "Default")
      (node (ref "TP11") (pin "1") (pinfunction "1_1") (pintype "passive"))
      (node (ref "U13") (pin "A2") (pinfunction "PE3_A2") (pintype "passive"))
    )
    (net (code "322") (name "/SCLK_MCLK") (class "Default")
      (node (ref "TP1") (pin "1") (pinfunction "1_1") (pintype "passive"))
    )
    (net (code "323") (name "/SPDIF_I2S") (class "Default")
      (node (ref "U13") (pin "N10") (pinfunction "PD11_N10") (pintype "passive"))
    )
    (net (code "324") (name "/SPDIF_RX") (class "Default")
      (node (ref "U13") (pin "C7") (pinfunction "PG12_C7") (pintype "passive"))
    )
    (net (code "325") (name "/SWCLK") (class "Default")
      (node (ref "U13") (pin "A14") (pinfunction "PA14_A14") (pintype "passive"))
    )
    (net (code "326") (name "/SWDIO") (class "Default")
      (node (ref "U13") (pin "A15") (pinfunction "PA13_A15") (pintype "passive"))
    )
    (net (code "327") (name "/SWO") (class "Default")
      (node (ref "R92") (pin "1") (pinfunction "1_1") (pintype "passive"))
    )
    (net (code "328") (name "/ULPI_CK") (class "Default")
      (node (ref "U13") (pin "P4") (pinfunction "PA5_P4") (pintype "passive"))
    )
    (net (code "329") (name "/ULPI_D0") (class "Default")
      (node (ref "U13") (pin "R2") (pinfunction "PA3_R2") (pintype "passive"))
    )
    (net (code "330") (name "/ULPI_D1") (class "Default")
      (node (ref "U13") (pin "R5") (pinfunction "PB0_R5") (pintype "passive"))
    )
    (net (code "331") (name "/ULPI_D2") (class "Default")
      (node (ref "U13") (pin "R4") (pinfunction "PB1_R4") (pintype "passive"))
    )
    (net (code "332") (name "/ULPI_D3") (class "Default")
      (node (ref "U13") (pin "P12") (pinfunction "PB10_P12") (pintype "passive"))
    )
    (net (code "333") (name "/ULPI_D4") (class "Default")
      (node (ref "U13") (pin "R13") (pinfunction "PB11_R13") (pintype "passive"))
    )
    (net (code "334") (name "/ULPI_D5") (class "Default")
      (node (ref "U13") (pin "L13") (pinfunction "PB12_L13") (pintype "passive"))
    )
    (net (code "335") (name "/ULPI_D6") (class "Default")
      (node (ref "U13") (pin "K14") (pinfunction "PB13_K14") (pintype "passive"))
    )
    (net (code "336") (name "/ULPI_D7") (class "Default")
      (node (ref "U13") (pin "A8") (pinfunction "PB5_A8") (pintype "passive"))
    )
    (net (code "337") (name "/ULPI_DIR") (class "Default")
      (node (ref "U13") (pin "F3") (pinfunction "PI11_F3") (pintype "passive"))
    )
    (net (code "339") (name "/ULPI_NXT") (class "Default")
      (node (ref "U13") (pin "H4") (pinfunction "PH4_H4") (pintype "passive"))
    )
    (net (code "340") (name "/ULPI_STP") (class "Default")
      (node (ref "U13") (pin "M2") (pinfunction "PC0_M2") (pintype "passive"))
    )
    (net (code "341") (name "/VCP_RX") (class "Default")
      (node (ref "U13") (pin "D15") (pinfunction "PA10_D15") (pintype "passive"))
    )
    (net (code "342") (name "/VCP_TX") (class "Default")
      (node (ref "U13") (pin "E15") (pinfunction "PA9_E15") (pintype "passive"))
    )
    (net (code "343") (name "/WIFI_RST") (class "Default")
      (node (ref "U13") (pin "C9") (pinfunction "PJ14_C9") (pintype "passive"))
    )
    (net (code "344") (name "/WIFI_RX") (class "Default")
      (node (ref "U13") (pin "A12") (pinfunction "PC12_A12") (pintype "passive"))
    )
    (net (code "345") (name "/WIFI_TX") (class "Default")
      (node (ref "U13") (pin "D12") (pinfunction "PD2_D12") (pintype "passive"))
    )
    (net (code "346") (name "/uSD_CLK") (class "Default")
      (node (ref "U13") (pin "B11") (pinfunction "PD6_B11") (pintype "passive"))
    )
    (net (code "347") (name "/uSD_CMD") (class "Default")
      (node (ref "U13") (pin "A11") (pinfunction "PD7_A11") (pintype "passive"))
    )
    (net (code "348") (name "/uSD_D0") (class "Default")
      (node (ref "U13") (pin "D9") (pinfunction "PG9_D9") (pintype "passive"))
    )
    (net (code "349") (name "/uSD_D1") (class "Default")
      (node (ref "U13") (pin "C8") (pinfunction "PG10_C8") (pintype "passive"))
    )
    (net (code "350") (name "/uSD_D2") (class "Default")
      (node (ref "R93") (pin "1") (pinfunction "1_1") (pintype "passive"))
    )
    (net (code "351") (name "/uSD_D3") (class "Default")
      (node (ref "U13") (pin "A9") (pinfunction "PB4_A9") (pintype "passive"))
    )
    (net (code "352") (name "/uSD_Detect") (class "Default")
      (node (ref "U13") (pin "G4") (pinfunction "PI15_G4") (pintype "passive"))
    )
    (net (code "354") (name "3V3") (class "Default")
      (node (ref "C98") (pin "2") (pinfunction "2_2") (pintype "passive"))
      (node (ref "JP4") (pin "2") (pinfunction "NO_2") (pintype "passive"))
      (node (ref "R106") (pin "2") (pinfunction "2_2") (pintype "passive"))
      (node (ref "R107") (pin "1") (pinfunction "1_1") (pintype "passive"))
      (node (ref "R109") (pin "2") (pinfunction "2_2") (pintype "passive"))
      (node (ref "R17") (pin "2") (pinfunction "2_2") (pintype "passive"))
      (node (ref "R19") (pin "1") (pinfunction "1_1") (pintype "passive"))
      (node (ref "R20") (pin "1") (pinfunction "1_1") (pintype "passive"))
      (node (ref "R89") (pin "1") (pinfunction "1_1") (pintype "passive"))
      (node (ref "R90") (pin "1") (pinfunction "1_1") (pintype "passive"))
      (node (ref "R91") (pin "1") (pinfunction "1_1") (pintype "passive"))
      (node (ref "X2") (pin "4") (pinfunction "VDD_4") (pintype "passive"))
    )
    (net (code "355") (name "DSI_VDD12") (class "Default")
      (node (ref "C23") (pin "2") (pinfunction "2_2") (pintype "passive"))
      (node (ref "C25") (pin "2") (pinfunction "2_2") (pintype "passive"))
      (node (ref "C27") (pin "2") (pinfunction "2_2") (pintype "passive"))
      (node (ref "U13") (pin "G13") (pinfunction "DSI_VDD12_0_G13") (pintype "power_in"))
      (node (ref "U13") (pin "K12") (pinfunction "DSI_VCAP_K12") (pintype "power_in"))
    )
    (net (code "356") (name "GND") (class "Default")
      (node (ref "C101") (pin "2") (pinfunction "2_2") (pintype "passive"))
      (node (ref "C102") (pin "1") (pinfunction "1_1") (pintype "passive"))
      (node (ref "C103") (pin "1") (pinfunction "1_1") (pintype "passive"))
      (node (ref "C104") (pin "1") (pinfunction "1_1") (pintype "passive"))
      (node (ref "C105") (pin "1") (pinfunction "1_1") (pintype "passive"))
      (node (ref "C106") (pin "1") (pinfunction "1_1") (pintype "passive"))
      (node (ref "C107") (pin "1") (pinfunction "1_1") (pintype "passive"))
      (node (ref "C108") (pin "1") (pinfunction "1_1") (pintype "passive"))
      (node (ref "C109") (pin "1") (pinfunction "1_1") (pintype "passive"))
      (node (ref "C110") (pin "1") (pinfunction "1_1") (pintype "passive"))
      (node (ref "C111") (pin "1") (pinfunction "1_1") (pintype "passive"))
      (node (ref "C112") (pin "1") (pinfunction "1_1") (pintype "passive"))
      (node (ref "C113") (pin "1") (pinfunction "1_1") (pintype "passive"))
      (node (ref "C114") (pin "1") (pinfunction "1_1") (pintype "passive"))
      (node (ref "C115") (pin "1") (pinfunction "1_1") (pintype "passive"))
      (node (ref "C116") (pin "2") (pinfunction "2_2") (pintype "passive"))
      (node (ref "C23") (pin "1") (pinfunction "1_1") (pintype "passive"))
      (node (ref "C25") (pin "1") (pinfunction "1_1") (pintype "passive"))
      (node (ref "C27") (pin "1") (pinfunction "1_1") (pintype "passive"))
      (node (ref "C31") (pin "1") (pinfunction "1_1") (pintype "passive"))
      (node (ref "C68") (pin "2") (pinfunction "2_2") (pintype "passive"))
      (node (ref "C69") (pin "2") (pinfunction "2_2") (pintype "passive"))
      (node (ref "C72") (pin "1") (pinfunction "1_1") (pintype "passive"))
      (node (ref "C76") (pin "1") (pinfunction "1_1") (pintype "passive"))
      (node (ref "C77") (pin "1") (pinfunction "1_1") (pintype "passive"))
      (node (ref "C80") (pin "1") (pinfunction "1_1") (pintype "passive"))
      (node (ref "C83") (pin "1") (pinfunction "1_1") (pintype "passive"))
      (node (ref "C84") (pin "1") (pinfunction "1_1") (pintype "passive"))
      (node (ref "C86") (pin "1") (pinfunction "1_1") (pintype "passive"))
      (node (ref "C88") (pin "1") (pinfunction "1_1") (pintype "passive"))
      (node (ref "C97") (pin "1") (pinfunction "1_1") (pintype "passive"))
      (node (ref "C98") (pin "1") (pinfunction "1_1") (pintype "passive"))
      (node (ref "C99") (pin "1") (pinfunction "1_1") (pintype "passive"))
      (node (ref "R108") (pin "1") (pinfunction "1_1") (pintype "passive"))
      (node (ref "R18") (pin "1") (pinfunction "1_1") (pintype "passive"))
      (node (ref "R21") (pin "1") (pinfunction "1_1") (pintype "passive"))
      (node (ref "U13") (pin "F10") (pinfunction "VSS2_F10") (pintype "passive"))
      (node (ref "U13") (pin "F2") (pinfunction "VSS13-VSS18_F2") (pintype "passive"))
      (node (ref "U13") (pin "F6") (pinfunction "VSS3_F6") (pintype "passive"))
      (node (ref "U13") (pin "F7") (pinfunction "VSS11_F7") (pintype "passive"))
      (node (ref "U13") (pin "F8") (pinfunction "VSS10_F8") (pintype "passive"))
      (node (ref "U13") (pin "F9") (pinfunction "VSS15_F9") (pintype "passive"))
      (node (ref "U13") (pin "G10") (pinfunction "VSS9_G10") (pintype "passive"))
      (node (ref "U13") (pin "G12") (pinfunction "DSI_VSS_G12") (pintype "power_in"))
      (node (ref "U13") (pin "G6") (pinfunction "VSS17_G6") (pintype "passive"))
      (node (ref "U13") (pin "H10") (pinfunction "VSS20_H10") (pintype "passive"))
      (node (ref "U13") (pin "H6") (pinfunction "VSS5_H6") (pintype "passive"))
      (node (ref "U13") (pin "J10") (pinfunction "VSS8_J10") (pintype "passive"))
      (node (ref "U13") (pin "J6") (pinfunction "VSS12_J6") (pintype "passive"))
      (node (ref "U13") (pin "K10") (pinfunction "VSS14_K10") (pintype "passive"))
      (node (ref "U13") (pin "K6") (pinfunction "VSS4_K6") (pintype "passive"))
      (node (ref "U13") (pin "K7") (pinfunction "VSS6_K7") (pintype "passive"))
      (node (ref "U13") (pin "K8") (pinfunction "VSS7_K8") (pintype "passive"))
      (node (ref "U13") (pin "K9") (pinfunction "VSS1_K9") (pintype "passive"))
      (node (ref "U13") (pin "L6") (pinfunction "VSS19_L6") (pintype "passive"))
      (node (ref "U13") (pin "M1") (pinfunction "VSSA_M1") (pintype "passive"))
      (node (ref "U13") (pin "N1") (pinfunction "VREF-_N1") (pintype "passive"))
      (node (ref "X2") (pin "2") (pinfunction "GND_2") (pintype "passive"))
    )
    (net (code "357") (name "Net-(C77-Pad2)") (class "Default")
      (node (ref "C77") (pin "2") (pinfunction "2_2") (pintype "passive"))
      (node (ref "R97") (pin "1") (pinfunction "1_1") (pintype "passive"))
      (node (ref "X1") (pin "1") (pinfunction "1_1") (pintype "passive"))
    )
    (net (code "358") (name "Net-(C84-Pad2)") (class "Default")
      (node (ref "C84") (pin "2") (pinfunction "2_2") (pintype "passive"))
      (node (ref "R99") (pin "1") (pinfunction "1_1") (pintype "passive"))
      (node (ref "X1") (pin "2") (pinfunction "2_2") (pintype "passive"))
    )
    (net (code "359") (name "Net-(U13A-PDR_ON)") (class "Default")
      (node (ref "R20") (pin "2") (pinfunction "2_2") (pintype "passive"))
      (node (ref "R21") (pin "2") (pinfunction "2_2") (pintype "passive"))
      (node (ref "U13") (pin "E5") (pinfunction "PDR_ON_E5") (pintype "passive"))
    )
    (net (code "360") (name "Net-(U13C-BYPASS-REG)") (class "Default")
      (node (ref "R108") (pin "2") (pinfunction "2_2") (pintype "passive"))
      (node (ref "U13") (pin "L5") (pinfunction "BYPASS-REG_L5") (pintype "passive"))
    )
    (net (code "361") (name "Net-(U13C-VCAP1)") (class "Default")
      (node (ref "C31") (pin "2") (pinfunction "2_2") (pintype "passive"))
      (node (ref "U13") (pin "L11") (pinfunction "VCAP1_L11") (pintype "passive"))
    )
    (net (code "362") (name "Net-(U13C-VCAP2)") (class "Default")
      (node (ref "C72") (pin "2") (pinfunction "2_2") (pintype "passive"))
      (node (ref "U13") (pin "E11") (pinfunction "VCAP2_E11") (pintype "passive"))
    )
    (net (code "363") (name "Net-(X2-EN)") (class "Default")
      (node (ref "R107") (pin "2") (pinfunction "2_2") (pintype "passive"))
      (node (ref "X2") (pin "1") (pinfunction "EN_1") (pintype "passive"))
    )
    (net (code "364") (name "VDD") (class "Default")
      (node (ref "C104") (pin "2") (pinfunction "2_2") (pintype "passive"))
      (node (ref "C105") (pin "2") (pinfunction "2_2") (pintype "passive"))
      (node (ref "C106") (pin "2") (pinfunction "2_2") (pintype "passive"))
      (node (ref "C107") (pin "2") (pinfunction "2_2") (pintype "passive"))
      (node (ref "C108") (pin "2") (pinfunction "2_2") (pintype "passive"))
      (node (ref "C109") (pin "2") (pinfunction "2_2") (pintype "passive"))
      (node (ref "C110") (pin "2") (pinfunction "2_2") (pintype "passive"))
      (node (ref "C111") (pin "2") (pinfunction "2_2") (pintype "passive"))
      (node (ref "C112") (pin "2") (pinfunction "2_2") (pintype "passive"))
      (node (ref "C113") (pin "2") (pinfunction "2_2") (pintype "passive"))
      (node (ref "C114") (pin "2") (pinfunction "2_2") (pintype "passive"))
      (node (ref "C115") (pin "2") (pinfunction "2_2") (pintype "passive"))
      (node (ref "C68") (pin "1") (pinfunction "1_1") (pintype "passive"))
      (node (ref "C69") (pin "1") (pinfunction "1_1") (pintype "passive"))
      (node (ref "C76") (pin "2") (pinfunction "2_2") (pintype "passive"))
      (node (ref "C80") (pin "2") (pinfunction "2_2") (pintype "passive"))
      (node (ref "C83") (pin "2") (pinfunction "2_2") (pintype "passive"))
      (node (ref "C86") (pin "2") (pinfunction "2_2") (pintype "passive"))
      (node (ref "C88") (pin "2") (pinfunction "2_2") (pintype "passive"))
      (node (ref "C97") (pin "2") (pinfunction "2_2") (pintype "passive"))
      (node (ref "C99") (pin "2") (pinfunction "2_2") (pintype "passive"))
      (node (ref "JP4") (pin "1") (pinfunction "COMMON_1") (pintype "passive"))
      (node (ref "L6") (pin "1") (pinfunction "1_1") (pintype "passive"))
      (node (ref "R109") (pin "1") (pinfunction "1_1") (pintype "passive"))
      (node (ref "U13") (pin "C1") (pinfunction "VBAT_C1") (pintype "passive"))
      (node (ref "U13") (pin "E10") (pinfunction "VDD15_E10") (pintype "passive"))
      (node (ref "U13") (pin "E7") (pinfunction "VDD3_E7") (pintype "passive"))
      (node (ref "U13") (pin "E8") (pinfunction "VDD11_E8") (pintype "passive"))
      (node (ref "U13") (pin "E9") (pinfunction "VDD_MMC33_E9") (pintype "passive"))
      (node (ref "U13") (pin "F11") (pinfunction "VDD2_F11") (pintype "passive"))
      (node (ref "U13") (pin "F4") (pinfunction "VDD13_F4") (pintype "passive"))
      (node (ref "U13") (pin "F5") (pinfunction "VDD17_F5") (pintype "passive"))
      (node (ref "U13") (pin "G11") (pinfunction "VDD_USB33_G11") (pintype "passive"))
      (node (ref "U13") (pin "G5") (pinfunction "VDD18_G5") (pintype "passive"))
      (node (ref "U13") (pin "H11") (pinfunction "VDD_VREGDSI_H11") (pintype "passive"))
      (node (ref "U13") (pin "H5") (pinfunction "VDD5_H5") (pintype "passive"))
      (node (ref "U13") (pin "J11") (pinfunction "VDD8_J11") (pintype "passive"))
      (node (ref "U13") (pin "J5") (pinfunction "VDD12_J5") (pintype "passive"))
      (node (ref "U13") (pin "K11") (pinfunction "VDD14_K11") (pintype "passive"))
      (node (ref "U13") (pin "K5") (pinfunction "VDD4_K5") (pintype "passive"))
      (node (ref "U13") (pin "L10") (pinfunction "VDD1_L10") (pintype "passive"))
      (node (ref "U13") (pin "L7") (pinfunction "VDD19_L7") (pintype "passive"))
      (node (ref "U13") (pin "L8") (pinfunction "VDD6_L8") (pintype "passive"))
      (node (ref "U13") (pin "L9") (pinfunction "VDD7_L9") (pintype "passive"))
    )
    (net (code "365") (name "VDDA") (class "Default")
      (node (ref "C103") (pin "2") (pinfunction "2_2") (pintype "passive"))
      (node (ref "C116") (pin "1") (pinfunction "1_1") (pintype "passive"))
      (node (ref "L6") (pin "2") (pinfunction "2_2") (pintype "passive"))
      (node (ref "R110") (pin "1") (pinfunction "1_1") (pintype "passive"))
      (node (ref "U13") (pin "R1") (pinfunction "VDDA_R1") (pintype "passive"))
    )
    (net (code "366") (name "VREF+") (class "Default")
      (node (ref "C101") (pin "1") (pinfunction "1_1") (pintype "passive"))
      (node (ref "C102") (pin "2") (pinfunction "2_2") (pintype "passive"))
      (node (ref "R110") (pin "2") (pinfunction "2_2") (pintype "passive"))
      (node (ref "U13") (pin "P1") (pinfunction "VREF+_P1") (pintype "passive"))
    )
  )
)
